# BWP08.net
KiCad netlist of a schematic drawn in Altium Designer
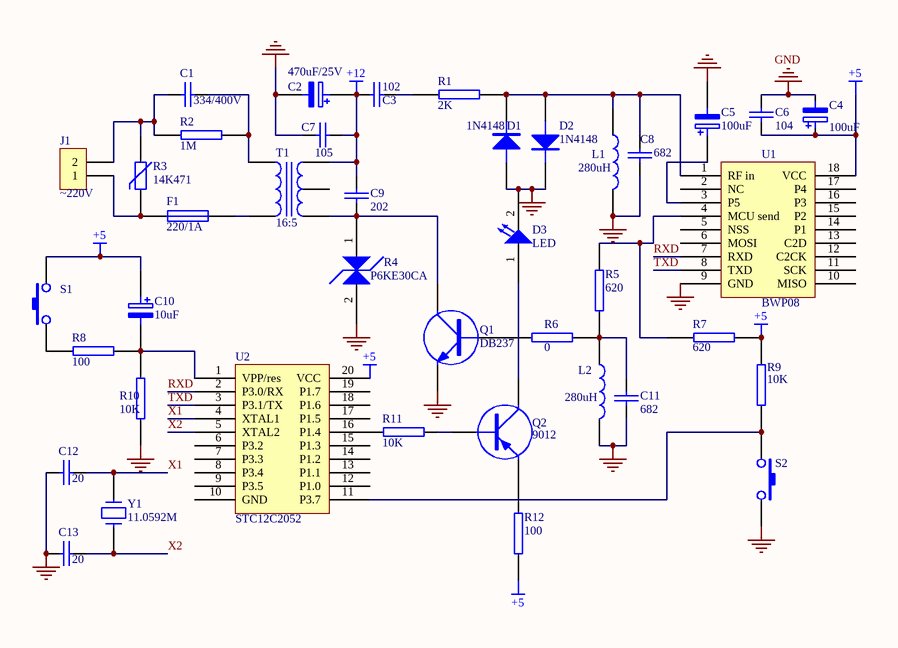
[diagram p0: BWP08.SCHDOC]

(export (version "E")
  (design (tool "Eeschema 10.0.6"))
  (components
    (comp (ref "C1")
      (value "334/400V")
      (footprint "CAP_CBB")
      (description "Capacitor")
      (libsource (lib "*") (part "CAP"))
    )
    (comp (ref "C2")
      (value "470uF/25V")
      (footprint "0805")
      (description "Electrolytic Capacitor")
      (libsource (lib "*") (part "ELECTRO2"))
    )
    (comp (ref "C3")
      (value "102")
      (footprint "0805")
      (description "Capacitor")
      (libsource (lib "*") (part "CAP"))
    )
    (comp (ref "C4")
      (value "100uF")
      (footprint "0805")
      (description "Electrolytic Capacitor")
      (libsource (lib "") (part "ELECTRO2_1"))
    )
    (comp (ref "C5")
      (value "100uF")
      (footprint "0805")
      (description "Electrolytic Capacitor")
      (libsource (lib "*") (part "ELECTRO2"))
    )
    (comp (ref "C6")
      (value "104")
      (footprint "0805")
      (description "Capacitor")
      (libsource (lib "*") (part "CAP"))
    )
    (comp (ref "C7")
      (value "105")
      (footprint "0805")
      (description "Capacitor")
      (libsource (lib "*") (part "CAP"))
    )
    (comp (ref "C8")
      (value "682")
      (footprint "0805")
      (description "Capacitor")
      (libsource (lib "*") (part "CAP"))
    )
    (comp (ref "C9")
      (value "202")
      (footprint "0805")
      (description "Capacitor")
      (libsource (lib "*") (part "CAP"))
    )
    (comp (ref "C10")
      (value "10uF")
      (footprint "RB.2/.4")
      (description "Electrolytic Capacitor")
      (libsource (lib "*") (part "ELECTRO2"))
    )
    (comp (ref "C11")
      (value "682")
      (footprint "0805")
      (description "Capacitor")
      (libsource (lib "*") (part "CAP"))
    )
    (comp (ref "C12")
      (value "20")
      (footprint "0805")
      (description "Capacitor")
      (libsource (lib "*") (part "CAP"))
    )
    (comp (ref "C13")
      (value "20")
      (footprint "0805")
      (description "Capacitor")
      (libsource (lib "*") (part "CAP"))
    )
    (comp (ref "D1")
      (value "1N4148")
      (footprint "SMT_DI")
      (description "Diode")
      (libsource (lib "*") (part "DIODE"))
    )
    (comp (ref "D2")
      (value "1N4148")
      (footprint "SMT_DI")
      (description "Diode")
      (libsource (lib "*") (part "DIODE"))
    )
    (comp (ref "D3") (value "LED") (footprint "RAD0.1") (libsource (lib "*") (part "LED")))
    (comp (ref "F1")
      (value "220/1A")
      (footprint "FUSE_R")
      (description "Fuse")
      (libsource (lib "*") (part "FUSE1"))
    )
    (comp (ref "J1")
      (value "~220V")
      (footprint "MY_MAIN")
      (description "Connector")
      (libsource (lib "*") (part "CON2"))
    )
    (comp (ref "L1") (value "280uH") (footprint "AXIAL0.4") (libsource (lib "*") (part "INDUCTOR1")))
    (comp (ref "L2") (value "280uH") (footprint "AXIAL0.4") (libsource (lib "*") (part "INDUCTOR1")))
    (comp (ref "Q1")
      (value "DB237")
      (footprint "TO-92B")
      (description "NPN Transistor")
      (libsource (lib "*") (part "NPN"))
    )
    (comp (ref "Q2")
      (value "9012")
      (footprint "SOT-23")
      (description "PNP Transistor")
      (libsource (lib "*") (part "PNP"))
    )
    (comp (ref "R1") (value "2K") (footprint "0805") (libsource (lib "*") (part "RES2")))
    (comp (ref "R2") (value "1M") (footprint "0805") (libsource (lib "*") (part "RES2")))
    (comp (ref "R3") (value "14K471") (footprint "PVR1") (libsource (lib "*") (part "VARISTOR")))
    (comp (ref "R4") (value "P6KE30CA") (footprint "SMBJ20") (libsource (lib "*") (part "YIZHIQI")))
    (comp (ref "R5") (value "620") (footprint "0805") (libsource (lib "*") (part "RES2")))
    (comp (ref "R6") (value "0") (footprint "0805") (libsource (lib "*") (part "RES2")))
    (comp (ref "R7") (value "620") (footprint "0805") (libsource (lib "*") (part "RES2")))
    (comp (ref "R8") (value "100") (footprint "0805") (libsource (lib "*") (part "RES2")))
    (comp (ref "R9") (value "10K") (footprint "0805") (libsource (lib "*") (part "RES2")))
    (comp (ref "R10") (value "10K") (footprint "0805") (libsource (lib "*") (part "RES2")))
    (comp (ref "R11") (value "10K") (footprint "0805") (libsource (lib "") (part "RES2_1")))
    (comp (ref "R12") (value "100") (footprint "0805") (libsource (lib "*") (part "RES2")))
    (comp (ref "S1") (value "~") (footprint "TT4") (libsource (lib "*") (part "SW-PB")))
    (comp (ref "S2") (value "~") (footprint "TT4") (libsource (lib "*") (part "SW-PB")))
    (comp (ref "T1") (value "16:5") (footprint "M5") (libsource (lib "*") (part "TRANS4")))
    (comp (ref "U1") (value "BWP08") (libsource (lib "*") (part "BWP08")))
    (comp (ref "U2") (value "STC12C2052") (footprint "DIP20") (libsource (lib "*") (part "STC12C4052")))
    (comp (ref "Y1")
      (value "11.0592M")
      (footprint "CRYSTAL_M")
      (description "Crystal")
      (libsource (lib "*") (part "CRYSTAL"))
    )
  )
  (nets
    (net (code "1") (name "+5") (class "Default")
      (node (ref "C10") (pin "1") (pinfunction "1_1") (pintype "passive"))
      (node (ref "C4") (pin "1") (pinfunction "1_1") (pintype "passive"))
      (node (ref "C6") (pin "1") (pinfunction "1_1") (pintype "passive"))
      (node (ref "R12") (pin "1") (pinfunction "1_1") (pintype "passive"))
      (node (ref "R7") (pin "1") (pinfunction "1_1") (pintype "passive"))
      (node (ref "R9") (pin "1") (pinfunction "1_1") (pintype "passive"))
      (node (ref "S1") (pin "2") (pinfunction "2_2") (pintype "passive"))
      (node (ref "U1") (pin "18") (pinfunction "VCC_18") (pintype "passive"))
      (node (ref "U2") (pin "20") (pinfunction "VCC_20") (pintype "passive"))
    )
    (net (code "2") (name "+12") (class "Default")
      (node (ref "C2") (pin "1") (pinfunction "1_1") (pintype "passive"))
      (node (ref "C3") (pin "1") (pinfunction "1_1") (pintype "passive"))
      (node (ref "C7") (pin "1") (pinfunction "1_1") (pintype "passive"))
      (node (ref "C9") (pin "1") (pinfunction "1_1") (pintype "passive"))
      (node (ref "T1") (pin "2") (pinfunction "2_2") (pintype "passive"))
    )
    (net (code "3") (name "/RXD") (class "Default")
      (node (ref "U1") (pin "7") (pinfunction "RXD_7") (pintype "passive"))
      (node (ref "U2") (pin "2") (pinfunction "P3.0/RX_2") (pintype "passive"))
    )
    (net (code "4") (name "/TXD") (class "Default")
      (node (ref "U1") (pin "8") (pinfunction "TXD_8") (pintype "passive"))
      (node (ref "U2") (pin "3") (pinfunction "P3.1/TX_3") (pintype "passive"))
    )
    (net (code "5") (name "/X1") (class "Default")
      (node (ref "C12") (pin "2") (pinfunction "2_2") (pintype "passive"))
      (node (ref "U2") (pin "4") (pinfunction "XTAL1_4") (pintype "passive"))
      (node (ref "Y1") (pin "2") (pinfunction "2_2") (pintype "passive"))
    )
    (net (code "6") (name "/X2") (class "Default")
      (node (ref "C13") (pin "2") (pinfunction "2_2") (pintype "passive"))
      (node (ref "U2") (pin "5") (pinfunction "XTAL2_5") (pintype "passive"))
      (node (ref "Y1") (pin "1") (pinfunction "1_1") (pintype "passive"))
    )
    (net (code "7") (name "GND") (class "Default")
      (node (ref "C11") (pin "2") (pinfunction "2_2") (pintype "passive"))
      (node (ref "C12") (pin "1") (pinfunction "1_1") (pintype "passive"))
      (node (ref "C13") (pin "1") (pinfunction "1_1") (pintype "passive"))
      (node (ref "C2") (pin "2") (pinfunction "2_2") (pintype "passive"))
      (node (ref "C4") (pin "2") (pinfunction "2_2") (pintype "passive"))
      (node (ref "C5") (pin "2") (pinfunction "2_2") (pintype "passive"))
      (node (ref "C6") (pin "2") (pinfunction "2_2") (pintype "passive"))
      (node (ref "C7") (pin "2") (pinfunction "2_2") (pintype "passive"))
      (node (ref "C8") (pin "2") (pinfunction "2_2") (pintype "passive"))
      (node (ref "D1") (pin "1") (pinfunction "A_1") (pintype "passive"))
      (node (ref "D2") (pin "2") (pinfunction "K_2") (pintype "passive"))
      (node (ref "D3") (pin "2") (pintype "passive"))
      (node (ref "L1") (pin "2") (pinfunction "2_2") (pintype "passive"))
      (node (ref "L2") (pin "2") (pinfunction "2_2") (pintype "passive"))
      (node (ref "Q1") (pin "3") (pinfunction "E_3") (pintype "passive"))
      (node (ref "R10") (pin "2") (pinfunction "2_2") (pintype "passive"))
      (node (ref "R4") (pin "2") (pintype "passive"))
      (node (ref "S2") (pin "2") (pinfunction "2_2") (pintype "passive"))
      (node (ref "U1") (pin "9") (pinfunction "GND_9") (pintype "passive"))
    )
    (net (code "8") (name "Net-(C1-Pad1)") (class "Default")
      (node (ref "C1") (pin "1") (pinfunction "1_1") (pintype "passive"))
      (node (ref "J1") (pin "2") (pinfunction "2_2") (pintype "passive"))
      (node (ref "R2") (pin "1") (pinfunction "1_1") (pintype "passive"))
      (node (ref "R3") (pin "1") (pinfunction "1_1") (pintype "passive"))
    )
    (net (code "9") (name "Net-(C1-Pad2)") (class "Default")
      (node (ref "C1") (pin "2") (pinfunction "2_2") (pintype "passive"))
      (node (ref "R2") (pin "2") (pinfunction "2_2") (pintype "passive"))
      (node (ref "T1") (pin "1") (pinfunction "1_1") (pintype "passive"))
    )
    (net (code "10") (name "Net-(C3-Pad2)") (class "Default")
      (node (ref "C3") (pin "2") (pinfunction "2_2") (pintype "passive"))
      (node (ref "R1") (pin "1") (pinfunction "1_1") (pintype "passive"))
    )
    (net (code "11") (name "Net-(C11-Pad1)") (class "Default")
      (node (ref "C11") (pin "1") (pinfunction "1_1") (pintype "passive"))
      (node (ref "L2") (pin "1") (pinfunction "1_1") (pintype "passive"))
      (node (ref "R5") (pin "1") (pinfunction "1_1") (pintype "passive"))
      (node (ref "R6") (pin "1") (pinfunction "1_1") (pintype "passive"))
    )
    (net (code "12") (name "Net-(D1-K)") (class "Default")
      (node (ref "C8") (pin "1") (pinfunction "1_1") (pintype "passive"))
      (node (ref "D1") (pin "2") (pinfunction "K_2") (pintype "passive"))
      (node (ref "D2") (pin "1") (pinfunction "A_1") (pintype "passive"))
      (node (ref "L1") (pin "1") (pinfunction "1_1") (pintype "passive"))
      (node (ref "R1") (pin "2") (pinfunction "2_2") (pintype "passive"))
      (node (ref "U1") (pin "1") (pinfunction "RF_in_1") (pintype "passive"))
    )
    (net (code "13") (name "Net-(F1-Pad1)") (class "Default")
      (node (ref "F1") (pin "1") (pinfunction "1_1") (pintype "passive"))
      (node (ref "T1") (pin "4") (pinfunction "4_4") (pintype "passive"))
    )
    (net (code "14") (name "Net-(F1-Pad2)") (class "Default")
      (node (ref "F1") (pin "2") (pinfunction "2_2") (pintype "passive"))
      (node (ref "J1") (pin "1") (pinfunction "1_1") (pintype "passive"))
      (node (ref "R3") (pin "2") (pinfunction "2_2") (pintype "passive"))
    )
    (net (code "15") (name "Net-(Q1-B)") (class "Default")
      (node (ref "Q1") (pin "1") (pinfunction "B_1") (pintype "passive"))
      (node (ref "R6") (pin "2") (pinfunction "2_2") (pintype "passive"))
    )
    (net (code "16") (name "Net-(Q1-C)") (class "Default")
      (node (ref "C9") (pin "2") (pinfunction "2_2") (pintype "passive"))
      (node (ref "Q1") (pin "2") (pinfunction "C_2") (pintype "passive"))
      (node (ref "R4") (pin "1") (pintype "passive"))
      (node (ref "T1") (pin "5") (pinfunction "5_5") (pintype "passive"))
    )
    (net (code "17") (name "Net-(Q2-B)") (class "Default")
      (node (ref "Q2") (pin "1") (pinfunction "B_1") (pintype "passive"))
      (node (ref "R11") (pin "1") (pinfunction "1_1") (pintype "passive"))
    )
    (net (code "18") (name "Net-(Q2-C)") (class "Default")
      (node (ref "D3") (pin "1") (pintype "passive"))
      (node (ref "Q2") (pin "3") (pinfunction "C_3") (pintype "passive"))
    )
    (net (code "19") (name "Net-(Q2-E)") (class "Default")
      (node (ref "Q2") (pin "2") (pinfunction "E_2") (pintype "passive"))
      (node (ref "R12") (pin "2") (pinfunction "2_2") (pintype "passive"))
    )
    (net (code "20") (name "Net-(R8-Pad2)") (class "Default")
      (node (ref "R8") (pin "2") (pinfunction "2_2") (pintype "passive"))
      (node (ref "S1") (pin "1") (pinfunction "1_1") (pintype "passive"))
    )
    (net (code "21") (name "Net-(U1-MCU_send)") (class "Default")
      (node (ref "R5") (pin "2") (pinfunction "2_2") (pintype "passive"))
      (node (ref "R7") (pin "2") (pinfunction "2_2") (pintype "passive"))
      (node (ref "U1") (pin "4") (pinfunction "MCU_send_4") (pintype "passive"))
    )
    (net (code "22") (name "Net-(U1-P5)") (class "Default")
      (node (ref "C5") (pin "1") (pinfunction "1_1") (pintype "passive"))
      (node (ref "U1") (pin "3") (pinfunction "P5_3") (pintype "passive"))
    )
    (net (code "23") (name "Net-(U2-P1.4)") (class "Default")
      (node (ref "R11") (pin "2") (pinfunction "2_2") (pintype "passive"))
      (node (ref "U2") (pin "16") (pinfunction "P1.4_16") (pintype "passive"))
    )
    (net (code "24") (name "Net-(U2-P3.7)") (class "Default")
      (node (ref "R9") (pin "2") (pinfunction "2_2") (pintype "passive"))
      (node (ref "S2") (pin "1") (pinfunction "1_1") (pintype "passive"))
      (node (ref "U2") (pin "11") (pinfunction "P3.7_11") (pintype "passive"))
    )
    (net (code "25") (name "Net-(U2-VPP{slash}res)") (class "Default")
      (node (ref "C10") (pin "2") (pinfunction "2_2") (pintype "passive"))
      (node (ref "R10") (pin "1") (pinfunction "1_1") (pintype "passive"))
      (node (ref "R8") (pin "1") (pinfunction "1_1") (pintype "passive"))
      (node (ref "U2") (pin "1") (pinfunction "VPP/res_1") (pintype "passive"))
    )
    (net (code "26") (name "unconnected-(T1-Pad3)") (class "Default")
      (node (ref "T1") (pin "3") (pinfunction "3_3") (pintype "passive"))
    )
    (net (code "27") (name "unconnected-(U1-C2CK-Pad12)") (class "Default")
      (node (ref "U1") (pin "12") (pinfunction "C2CK_12") (pintype "passive"))
    )
    (net (code "28") (name "unconnected-(U1-C2D-Pad13)") (class "Default")
      (node (ref "U1") (pin "13") (pinfunction "C2D_13") (pintype "passive"))
    )
    (net (code "29") (name "unconnected-(U1-MISO-Pad10)") (class "Default")
      (node (ref "U1") (pin "10") (pinfunction "MISO_10") (pintype "passive"))
    )
    (net (code "30") (name "unconnected-(U1-MOSI-Pad6)") (class "Default")
      (node (ref "U1") (pin "6") (pinfunction "MOSI_6") (pintype "passive"))
    )
    (net (code "31") (name "unconnected-(U1-NC-Pad2)") (class "Default")
      (node (ref "U1") (pin "2") (pinfunction "NC_2") (pintype "passive"))
    )
    (net (code "32") (name "unconnected-(U1-NSS-Pad5)") (class "Default")
      (node (ref "U1") (pin "5") (pinfunction "NSS_5") (pintype "passive"))
    )
    (net (code "33") (name "unconnected-(U1-P1-Pad14)") (class "Default")
      (node (ref "U1") (pin "14") (pinfunction "P1_14") (pintype "passive"))
    )
    (net (code "34") (name "unconnected-(U1-P2-Pad15)") (class "Default")
      (node (ref "U1") (pin "15") (pinfunction "P2_15") (pintype "passive"))
    )
    (net (code "35") (name "unconnected-(U1-P3-Pad16)") (class "Default")
      (node (ref "U1") (pin "16") (pinfunction "P3_16") (pintype "passive"))
    )
    (net (code "36") (name "unconnected-(U1-P4-Pad17)") (class "Default")
      (node (ref "U1") (pin "17") (pinfunction "P4_17") (pintype "passive"))
    )
    (net (code "37") (name "unconnected-(U1-SCK-Pad11)") (class "Default")
      (node (ref "U1") (pin "11") (pinfunction "SCK_11") (pintype "passive"))
    )
    (net (code "38") (name "unconnected-(U2-GND-Pad10)") (class "Default")
      (node (ref "U2") (pin "10") (pinfunction "GND_10") (pintype "passive"))
    )
    (net (code "39") (name "unconnected-(U2-P1.0-Pad12)") (class "Default")
      (node (ref "U2") (pin "12") (pinfunction "P1.0_12") (pintype "passive"))
    )
    (net (code "40") (name "unconnected-(U2-P1.1-Pad13)") (class "Default")
      (node (ref "U2") (pin "13") (pinfunction "P1.1_13") (pintype "passive"))
    )
    (net (code "41") (name "unconnected-(U2-P1.2-Pad14)") (class "Default")
      (node (ref "U2") (pin "14") (pinfunction "P1.2_14") (pintype "passive"))
    )
    (net (code "42") (name "unconnected-(U2-P1.3-Pad15)") (class "Default")
      (node (ref "U2") (pin "15") (pinfunction "P1.3_15") (pintype "passive"))
    )
    (net (code "43") (name "unconnected-(U2-P1.5-Pad17)") (class "Default")
      (node (ref "U2") (pin "17") (pinfunction "P1.5_17") (pintype "passive"))
    )
    (net (code "44") (name "unconnected-(U2-P1.6-Pad18)") (class "Default")
      (node (ref "U2") (pin "18") (pinfunction "P1.6_18") (pintype "passive"))
    )
    (net (code "45") (name "unconnected-(U2-P1.7-Pad19)") (class "Default")
      (node (ref "U2") (pin "19") (pinfunction "P1.7_19") (pintype "passive"))
    )
    (net (code "46") (name "unconnected-(U2-P3.2-Pad6)") (class "Default")
      (node (ref "U2") (pin "6") (pinfunction "P3.2_6") (pintype "passive"))
    )
    (net (code "47") (name "unconnected-(U2-P3.3-Pad7)") (class "Default")
      (node (ref "U2") (pin "7") (pinfunction "P3.3_7") (pintype "passive"))
    )
    (net (code "48") (name "unconnected-(U2-P3.4-Pad8)") (class "Default")
      (node (ref "U2") (pin "8") (pinfunction "P3.4_8") (pintype "passive"))
    )
    (net (code "49") (name "unconnected-(U2-P3.5-Pad9)") (class "Default")
      (node (ref "U2") (pin "9") (pinfunction "P3.5_9") (pintype "passive"))
    )
  )
)
